# XLIN1_7-2048SQ_TE0_MEZ.net
KiCad netlist of a schematic drawn in Altium Designer
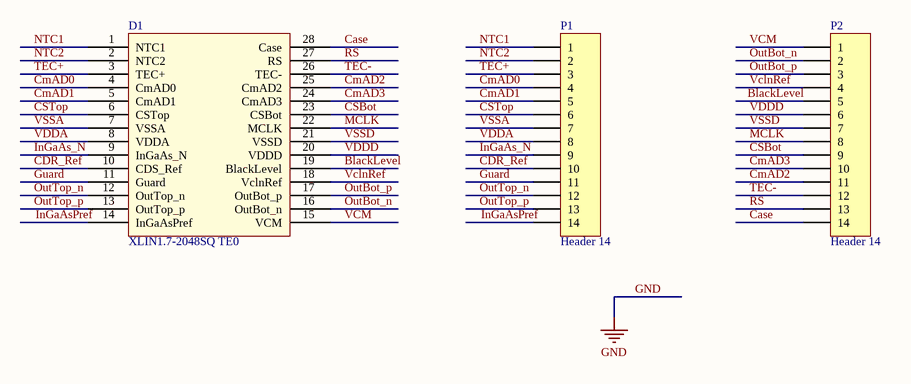
[diagram p0: XLIN1.7-2048SQ TE0_MEZ.SchDoc]

(export (version "E")
  (design (tool "Eeschema 10.0.6"))
  (components
    (comp (ref "D1")
      (value "XLIN1.7-2048SQ TE0")
      (footprint "aab_Active:XLIN1.7-2048SQ TE0")
      (libsource (lib "aab_Schlib") (part "XLIN1.7-2048SQ TE0"))
    )
    (comp (ref "P1")
      (value "Header 14")
      (footprint "HDR1X14")
      (description "Header, 14-Pin")
      (fields (field (name "PUBLISHER") "Altium Limited"))
      (libsource (lib "Miscellaneous Connectors") (part "Header 14"))
    )
    (comp (ref "P2")
      (value "Header 14")
      (footprint "HDR1X14")
      (description "Header, 14-Pin")
      (fields (field (name "PUBLISHER") "Altium Limited"))
      (libsource (lib "Miscellaneous Connectors") (part "Header 14"))
    )
  )
  (nets
    (net (code "1") (name "/BlackLevel") (class "Default")
      (node (ref "D1") (pin "19") (pinfunction "BlackLevel_19") (pintype "passive"))
      (node (ref "P2") (pin "5") (pinfunction "5_5") (pintype "passive"))
    )
    (net (code "2") (name "/CDR_Ref") (class "Default")
      (node (ref "D1") (pin "10") (pinfunction "CDS_Ref_10") (pintype "passive"))
      (node (ref "P1") (pin "10") (pinfunction "10_10") (pintype "passive"))
    )
    (net (code "3") (name "/CSBot") (class "Default")
      (node (ref "D1") (pin "23") (pinfunction "CSBot_23") (pintype "passive"))
      (node (ref "P2") (pin "9") (pinfunction "9_9") (pintype "passive"))
    )
    (net (code "4") (name "/CSTop") (class "Default")
      (node (ref "D1") (pin "6") (pinfunction "CSTop_6") (pintype "passive"))
      (node (ref "P1") (pin "6") (pinfunction "6_6") (pintype "passive"))
    )
    (net (code "5") (name "/Case") (class "Default")
      (node (ref "D1") (pin "28") (pinfunction "Case_28") (pintype "passive"))
      (node (ref "P2") (pin "14") (pinfunction "14_14") (pintype "passive"))
    )
    (net (code "6") (name "/CmAD0") (class "Default")
      (node (ref "D1") (pin "4") (pinfunction "CmAD0_4") (pintype "passive"))
      (node (ref "P1") (pin "4") (pinfunction "4_4") (pintype "passive"))
    )
    (net (code "7") (name "/CmAD1") (class "Default")
      (node (ref "D1") (pin "5") (pinfunction "CmAD1_5") (pintype "passive"))
      (node (ref "P1") (pin "5") (pinfunction "5_5") (pintype "passive"))
    )
    (net (code "8") (name "/CmAD2") (class "Default")
      (node (ref "D1") (pin "25") (pinfunction "CmAD2_25") (pintype "passive"))
      (node (ref "P2") (pin "11") (pinfunction "11_11") (pintype "passive"))
    )
    (net (code "9") (name "/CmAD3") (class "Default")
      (node (ref "D1") (pin "24") (pinfunction "CmAD3_24") (pintype "passive"))
      (node (ref "P2") (pin "10") (pinfunction "10_10") (pintype "passive"))
    )
    (net (code "10") (name "/Guard") (class "Default")
      (node (ref "D1") (pin "11") (pinfunction "Guard_11") (pintype "passive"))
      (node (ref "P1") (pin "11") (pinfunction "11_11") (pintype "passive"))
    )
    (net (code "11") (name "/InGaAsPref") (class "Default")
      (node (ref "D1") (pin "14") (pinfunction "InGaAsPref_14") (pintype "passive"))
      (node (ref "P1") (pin "14") (pinfunction "14_14") (pintype "passive"))
    )
    (net (code "12") (name "/InGaAs_N") (class "Default")
      (node (ref "D1") (pin "9") (pinfunction "InGaAs_N_9") (pintype "passive"))
      (node (ref "P1") (pin "9") (pinfunction "9_9") (pintype "passive"))
    )
    (net (code "13") (name "/MCLK") (class "Default")
      (node (ref "D1") (pin "22") (pinfunction "MCLK_22") (pintype "passive"))
      (node (ref "P2") (pin "8") (pinfunction "8_8") (pintype "passive"))
    )
    (net (code "14") (name "/NTC1") (class "Default")
      (node (ref "D1") (pin "1") (pinfunction "NTC1_1") (pintype "passive"))
      (node (ref "P1") (pin "1") (pinfunction "1_1") (pintype "passive"))
    )
    (net (code "15") (name "/NTC2") (class "Default")
      (node (ref "D1") (pin "2") (pinfunction "NTC2_2") (pintype "passive"))
      (node (ref "P1") (pin "2") (pinfunction "2_2") (pintype "passive"))
    )
    (net (code "16") (name "/OutBot_n") (class "Default")
      (node (ref "D1") (pin "16") (pinfunction "OutBot_n_16") (pintype "passive"))
      (node (ref "P2") (pin "2") (pinfunction "2_2") (pintype "passive"))
    )
    (net (code "17") (name "/OutBot_p") (class "Default")
      (node (ref "D1") (pin "17") (pinfunction "OutBot_p_17") (pintype "passive"))
      (node (ref "P2") (pin "3") (pinfunction "3_3") (pintype "passive"))
    )
    (net (code "18") (name "/OutTop_n") (class "Default")
      (node (ref "D1") (pin "12") (pinfunction "OutTop_n_12") (pintype "passive"))
      (node (ref "P1") (pin "12") (pinfunction "12_12") (pintype "passive"))
    )
    (net (code "19") (name "/OutTop_p") (class "Default")
      (node (ref "D1") (pin "13") (pinfunction "OutTop_p_13") (pintype "passive"))
      (node (ref "P1") (pin "13") (pinfunction "13_13") (pintype "passive"))
    )
    (net (code "20") (name "/RS") (class "Default")
      (node (ref "D1") (pin "27") (pinfunction "RS_27") (pintype "passive"))
      (node (ref "P2") (pin "13") (pinfunction "13_13") (pintype "passive"))
    )
    (net (code "21") (name "/TEC+") (class "Default")
      (node (ref "D1") (pin "3") (pinfunction "TEC+_3") (pintype "passive"))
      (node (ref "P1") (pin "3") (pinfunction "3_3") (pintype "passive"))
    )
    (net (code "22") (name "/TEC-") (class "Default")
      (node (ref "D1") (pin "26") (pinfunction "TEC-_26") (pintype "passive"))
      (node (ref "P2") (pin "12") (pinfunction "12_12") (pintype "passive"))
    )
    (net (code "23") (name "/VCM") (class "Default")
      (node (ref "D1") (pin "15") (pinfunction "VCM_15") (pintype "passive"))
      (node (ref "P2") (pin "1") (pinfunction "1_1") (pintype "passive"))
    )
    (net (code "24") (name "/VDDA") (class "Default")
      (node (ref "D1") (pin "8") (pinfunction "VDDA_8") (pintype "passive"))
      (node (ref "P1") (pin "8") (pinfunction "8_8") (pintype "passive"))
    )
    (net (code "25") (name "/VDDD") (class "Default")
      (node (ref "D1") (pin "20") (pinfunction "VDDD_20") (pintype "passive"))
      (node (ref "P2") (pin "6") (pinfunction "6_6") (pintype "passive"))
    )
    (net (code "26") (name "/VSSA") (class "Default")
      (node (ref "D1") (pin "7") (pinfunction "VSSA_7") (pintype "passive"))
      (node (ref "P1") (pin "7") (pinfunction "7_7") (pintype "passive"))
    )
    (net (code "27") (name "/VSSD") (class "Default")
      (node (ref "D1") (pin "21") (pinfunction "VSSD_21") (pintype "passive"))
      (node (ref "P2") (pin "7") (pinfunction "7_7") (pintype "passive"))
    )
    (net (code "28") (name "/VclnRef") (class "Default")
      (node (ref "D1") (pin "18") (pinfunction "VclnRef_18") (pintype "passive"))
      (node (ref "P2") (pin "4") (pinfunction "4_4") (pintype "passive"))
    )
  )
)
